# 2022-LPC2148_Piggyback_V1.net
KiCad netlist of a schematic drawn in EAGLE
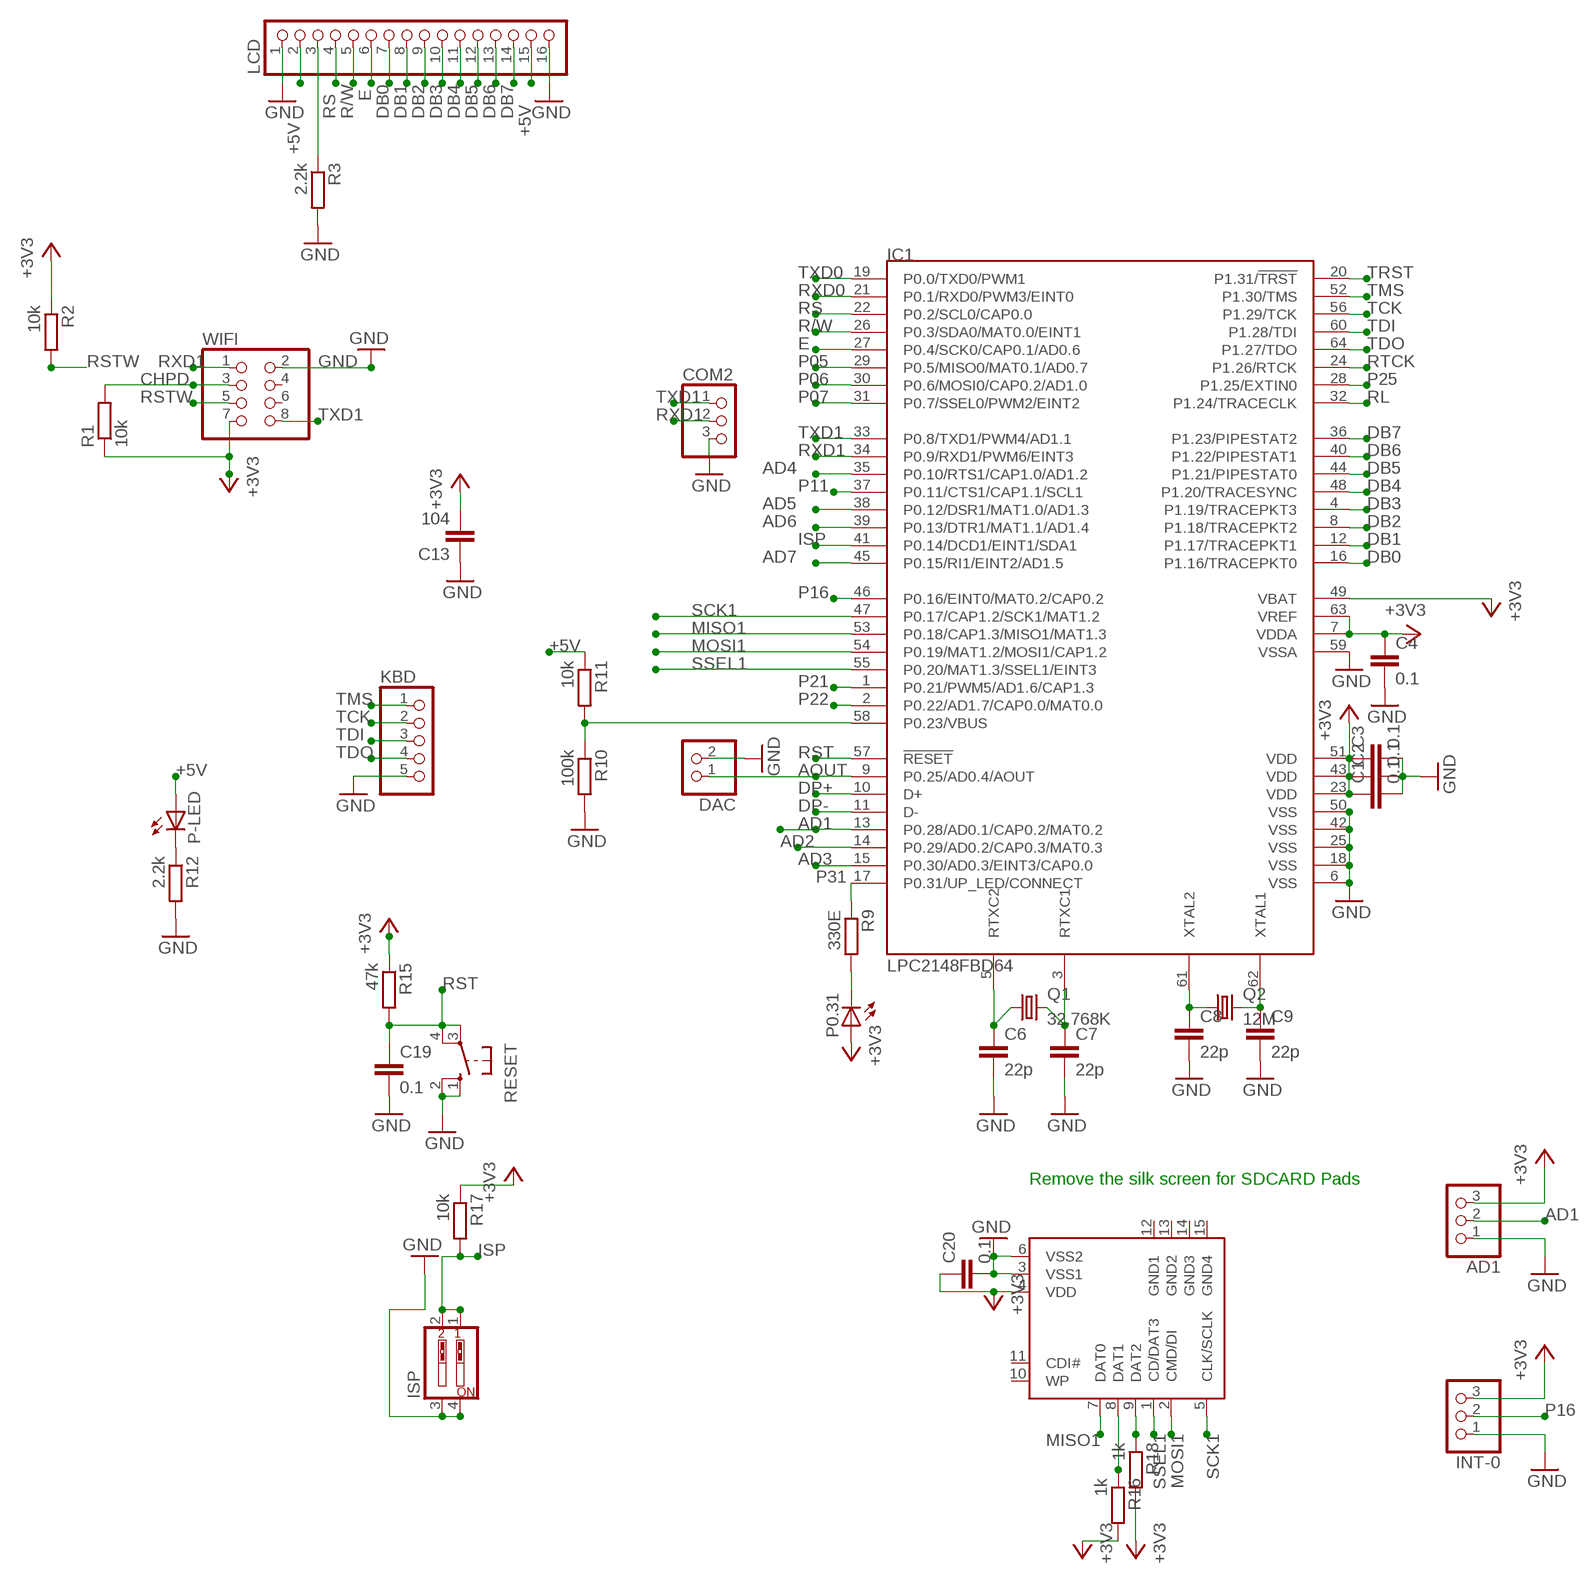
[diagram p0: schematic, sheet 1]
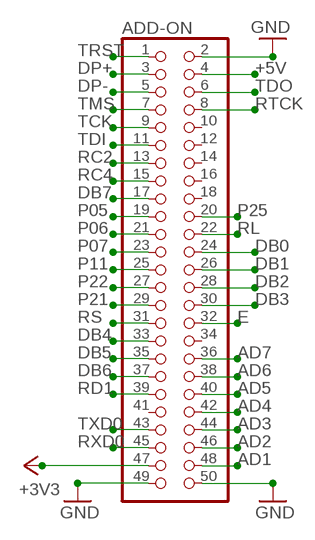
[diagram p1: schematic, sheet 2]
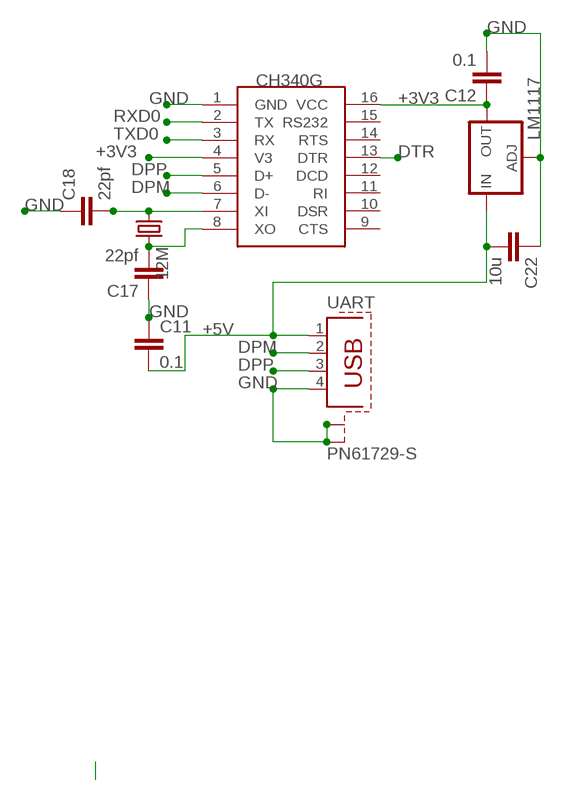
[diagram p2: schematic, sheet 3]

(export (version "E")
  (design (tool "Eeschema 10.0.6"))
  (components
    (comp (ref "AD1")
      (value "PINHD-1X3")
      (footprint "eagle-import:1X03")
      (libsource (lib "eagle-import") (part "PINHD-1X3"))
    )
    (comp (ref "C1")
      (value "0.1")
      (footprint "eagle-import:C1206")
      (libsource (lib "eagle-import") (part "C-EUC1206"))
    )
    (comp (ref "C2")
      (value "0.1")
      (footprint "eagle-import:C1206")
      (libsource (lib "eagle-import") (part "C-EUC1206"))
    )
    (comp (ref "C3")
      (value "0.1")
      (footprint "eagle-import:C1206")
      (libsource (lib "eagle-import") (part "C-EUC1206"))
    )
    (comp (ref "C4")
      (value "0.1")
      (footprint "eagle-import:C1206")
      (libsource (lib "eagle-import") (part "C-EUC1206"))
    )
    (comp (ref "C6")
      (value "22p")
      (footprint "eagle-import:C1206")
      (libsource (lib "eagle-import") (part "C-EUC1206"))
    )
    (comp (ref "C7")
      (value "22p")
      (footprint "eagle-import:C1206")
      (libsource (lib "eagle-import") (part "C-EUC1206"))
    )
    (comp (ref "C8")
      (value "22p")
      (footprint "eagle-import:C1206")
      (libsource (lib "eagle-import") (part "C-EUC1206"))
    )
    (comp (ref "C9")
      (value "22p")
      (footprint "eagle-import:C1206")
      (libsource (lib "eagle-import") (part "C-EUC1206"))
    )
    (comp (ref "C13")
      (value "104")
      (footprint "eagle-import:C1206")
      (libsource (lib "eagle-import") (part "C-EUC1206"))
    )
    (comp (ref "C19")
      (value "0.1")
      (footprint "eagle-import:C1206")
      (libsource (lib "eagle-import") (part "C-EUC1206"))
    )
    (comp (ref "C20")
      (value "0.1")
      (footprint "eagle-import:C1206")
      (libsource (lib "eagle-import") (part "C-EUC1206"))
    )
    (comp (ref "COM2")
      (value "PINHD-1X3")
      (footprint "eagle-import:1X03")
      (libsource (lib "eagle-import") (part "PINHD-1X3"))
    )
    (comp (ref "DAC")
      (value "PINHD-1X2")
      (footprint "eagle-import:1X02")
      (libsource (lib "eagle-import") (part "PINHD-1X2"))
    )
    (comp (ref "IC1")
      (value "LPC2148FBD64")
      (footprint "eagle-import:TSQFP50P1200X1200X160-64N")
      (libsource (lib "eagle-import") (part "LPC2148FBD64"))
    )
    (comp (ref "INT-0")
      (value "PINHD-1X3")
      (footprint "eagle-import:1X03")
      (libsource (lib "eagle-import") (part "PINHD-1X3"))
    )
    (comp (ref "ISP")
      (value "SW_DIP-2")
      (footprint "eagle-import:EDG-02")
      (libsource (lib "eagle-import") (part "SW_DIP-2"))
    )
    (comp (ref "KBD")
      (value "PINHD-1X5")
      (footprint "eagle-import:1X05")
      (libsource (lib "eagle-import") (part "PINHD-1X5"))
    )
    (comp (ref "LCD")
      (value "PINHD-1X16")
      (footprint "eagle-import:1X16")
      (libsource (lib "eagle-import") (part "PINHD-1X16"))
    )
    (comp (ref "P-LED")
      (value "LEDCHIPLED_1206")
      (footprint "eagle-import:CHIPLED_1206")
      (libsource (lib "eagle-import") (part "LEDCHIPLED_1206"))
    )
    (comp (ref "P0.31")
      (value "LEDCHIPLED_1206")
      (footprint "eagle-import:CHIPLED_1206")
      (libsource (lib "eagle-import") (part "LEDCHIPLED_1206"))
    )
    (comp (ref "Q1")
      (value "32.768K")
      (footprint "eagle-import:TC26H")
      (libsource (lib "eagle-import") (part "CRYSTALTC26H"))
    )
    (comp (ref "Q2")
      (value "12M")
      (footprint "eagle-import:HC49U70")
      (libsource (lib "eagle-import") (part "CRYSTALHC49U70"))
    )
    (comp (ref "R1")
      (value "10k")
      (footprint "eagle-import:R1206")
      (libsource (lib "eagle-import") (part "R-EU_R1206"))
    )
    (comp (ref "R2")
      (value "10k")
      (footprint "eagle-import:R1206")
      (libsource (lib "eagle-import") (part "R-EU_R1206"))
    )
    (comp (ref "R3")
      (value "2.2k")
      (footprint "eagle-import:R1206")
      (libsource (lib "eagle-import") (part "R-EU_R1206"))
    )
    (comp (ref "R9")
      (value "330E")
      (footprint "eagle-import:R1206")
      (libsource (lib "eagle-import") (part "R-EU_R1206"))
    )
    (comp (ref "R10")
      (value "100k")
      (footprint "eagle-import:R1206")
      (libsource (lib "eagle-import") (part "R-EU_R1206"))
    )
    (comp (ref "R11")
      (value "10k")
      (footprint "eagle-import:R1206")
      (libsource (lib "eagle-import") (part "R-EU_R1206"))
    )
    (comp (ref "R12")
      (value "2.2k")
      (footprint "eagle-import:R1206")
      (libsource (lib "eagle-import") (part "R-EU_R1206"))
    )
    (comp (ref "R15")
      (value "47k")
      (footprint "eagle-import:R1206")
      (libsource (lib "eagle-import") (part "R-EU_R1206"))
    )
    (comp (ref "R16")
      (value "1k")
      (footprint "eagle-import:R1206")
      (libsource (lib "eagle-import") (part "R-EU_R1206"))
    )
    (comp (ref "R17")
      (value "10k")
      (footprint "eagle-import:R1206")
      (libsource (lib "eagle-import") (part "R-EU_R1206"))
    )
    (comp (ref "R18")
      (value "1k")
      (footprint "eagle-import:R1206")
      (libsource (lib "eagle-import") (part "R-EU_R1206"))
    )
    (comp (ref "RESET")
      (value "10-XX")
      (footprint "eagle-import:B3F-10XX")
      (fields (field (name "MPN") "B3F-1000"))
      (libsource (lib "eagle-import") (part "10-XX"))
    )
    (comp (ref "SD")
      (value "SDCARDVAR2")
      (footprint "eagle-import:SDCMF-10915W010")
      (libsource (lib "eagle-import") (part "SDCARDVAR2"))
    )
    (comp (ref "WIFI")
      (value "PINHD-2X4")
      (footprint "eagle-import:2X04")
      (libsource (lib "eagle-import") (part "PINHD-2X4"))
    )
    (comp (ref "ADD-ON")
      (value "PINHD-2X25")
      (footprint "eagle-import:2X25")
      (libsource (lib "eagle-import") (part "PINHD-2X25"))
    )
    (comp (ref "12M")
      (value "CRYSTALHC18U-V")
      (footprint "eagle-import:HC18U-V")
      (libsource (lib "eagle-import") (part "CRYSTALHC18U-V"))
    )
    (comp (ref "C11")
      (value "0.1")
      (footprint "eagle-import:C1206")
      (libsource (lib "eagle-import") (part "C-EUC1206"))
    )
    (comp (ref "C12")
      (value "0.1")
      (footprint "eagle-import:C1206")
      (libsource (lib "eagle-import") (part "C-EUC1206"))
    )
    (comp (ref "C17")
      (value "22pf")
      (footprint "eagle-import:C1206")
      (libsource (lib "eagle-import") (part "C-EUC1206"))
    )
    (comp (ref "C18")
      (value "22pf")
      (footprint "eagle-import:C1206")
      (libsource (lib "eagle-import") (part "C-EUC1206"))
    )
    (comp (ref "C22")
      (value "10u")
      (footprint "eagle-import:C1206")
      (libsource (lib "eagle-import") (part "C-EUC1206"))
    )
    (comp (ref "LM1117")
      (value "LD117AS18TR")
      (footprint "eagle-import:SOT223")
      (libsource (lib "eagle-import") (part "LD117A?S18TR"))
    )
    (comp (ref "U$1")
      (value "CH340G")
      (footprint "eagle-import:SOIC16")
      (libsource (lib "eagle-import") (part "CH340G"))
    )
    (comp (ref "UART")
      (value "PN61729-S")
      (footprint "eagle-import:PN61729-S")
      (libsource (lib "eagle-import") (part "PN61729-S"))
    )
  )
  (nets
    (net (code "1") (name "+3V3") (class "Default")
      (node (ref "AD1") (pin "3") (pinfunction "3_3") (pintype "passive"))
      (node (ref "ADD-ON") (pin "47") (pinfunction "47_47") (pintype "passive"))
      (node (ref "C1") (pin "1") (pinfunction "1_1") (pintype "passive"))
      (node (ref "C12") (pin "1") (pinfunction "1_1") (pintype "passive"))
      (node (ref "C13") (pin "2") (pinfunction "2_2") (pintype "passive"))
      (node (ref "C2") (pin "1") (pinfunction "1_1") (pintype "passive"))
      (node (ref "C20") (pin "1") (pinfunction "1_1") (pintype "passive"))
      (node (ref "C3") (pin "1") (pinfunction "1_1") (pintype "passive"))
      (node (ref "C4") (pin "1") (pinfunction "1_1") (pintype "passive"))
      (node (ref "IC1") (pin "23") (pinfunction "VDD_23") (pintype "power_in"))
      (node (ref "IC1") (pin "43") (pinfunction "VDD_43") (pintype "power_in"))
      (node (ref "IC1") (pin "49") (pinfunction "VBAT_49") (pintype "power_in"))
      (node (ref "IC1") (pin "51") (pinfunction "VDD_51") (pintype "power_in"))
      (node (ref "IC1") (pin "63") (pinfunction "VREF_63") (pintype "input"))
      (node (ref "IC1") (pin "7") (pinfunction "VDDA_7") (pintype "power_in"))
      (node (ref "INT-0") (pin "3") (pinfunction "3_3") (pintype "passive"))
      (node (ref "LM1117") (pin "4") (pinfunction "OUT_4") (pintype "passive"))
      (node (ref "P0.31") (pin "A") (pinfunction "A_A") (pintype "passive"))
      (node (ref "R1") (pin "1") (pinfunction "1_1") (pintype "passive"))
      (node (ref "R15") (pin "1") (pinfunction "1_1") (pintype "passive"))
      (node (ref "R16") (pin "2") (pinfunction "2_2") (pintype "passive"))
      (node (ref "R17") (pin "1") (pinfunction "1_1") (pintype "passive"))
      (node (ref "R18") (pin "2") (pinfunction "2_2") (pintype "passive"))
      (node (ref "R2") (pin "1") (pinfunction "1_1") (pintype "passive"))
      (node (ref "SD") (pin "4") (pinfunction "VDD_4") (pintype "power_in"))
      (node (ref "U$1") (pin "16") (pinfunction "VCC_16") (pintype "bidirectional"))
      (node (ref "U$1") (pin "4") (pinfunction "V3_4") (pintype "bidirectional"))
      (node (ref "WIFI") (pin "7") (pinfunction "7_7") (pintype "passive"))
    )
    (net (code "2") (name "+5V") (class "Default")
      (node (ref "ADD-ON") (pin "4") (pinfunction "4_4") (pintype "passive"))
      (node (ref "C11") (pin "2") (pinfunction "2_2") (pintype "passive"))
      (node (ref "C22") (pin "2") (pinfunction "2_2") (pintype "passive"))
      (node (ref "LCD") (pin "15") (pinfunction "15_15") (pintype "passive"))
      (node (ref "LCD") (pin "2") (pinfunction "2_2") (pintype "passive"))
      (node (ref "LM1117") (pin "3") (pinfunction "IN_3") (pintype "input"))
      (node (ref "P-LED") (pin "A") (pinfunction "A_A") (pintype "passive"))
      (node (ref "R11") (pin "1") (pinfunction "1_1") (pintype "passive"))
      (node (ref "UART") (pin "1") (pinfunction "1_1") (pintype "passive"))
    )
    (net (code "3") (name "AD1") (class "Default")
      (node (ref "AD1") (pin "2") (pinfunction "2_2") (pintype "passive"))
      (node (ref "ADD-ON") (pin "48") (pinfunction "48_48") (pintype "passive"))
      (node (ref "IC1") (pin "13") (pinfunction "P0.28/AD0.1/CAP0.2/MAT0.2_13") (pintype "bidirectional"))
    )
    (net (code "4") (name "AD2") (class "Default")
      (node (ref "ADD-ON") (pin "46") (pinfunction "46_46") (pintype "passive"))
      (node (ref "IC1") (pin "14") (pinfunction "P0.29/AD0.2/CAP0.3/MAT0.3_14") (pintype "bidirectional"))
    )
    (net (code "5") (name "AD3") (class "Default")
      (node (ref "ADD-ON") (pin "44") (pinfunction "44_44") (pintype "passive"))
      (node (ref "IC1") (pin "15") (pinfunction "P0.30/AD0.3/EINT3/CAP0.0_15") (pintype "bidirectional"))
    )
    (net (code "6") (name "AD4") (class "Default")
      (node (ref "ADD-ON") (pin "42") (pinfunction "42_42") (pintype "passive"))
      (node (ref "IC1") (pin "35") (pinfunction "P0.10/RTS1/CAP1.0/AD1.2_35") (pintype "bidirectional"))
    )
    (net (code "7") (name "AD5") (class "Default")
      (node (ref "ADD-ON") (pin "40") (pinfunction "40_40") (pintype "passive"))
      (node (ref "IC1") (pin "38") (pinfunction "P0.12/DSR1/MAT1.0/AD1.3_38") (pintype "bidirectional"))
    )
    (net (code "8") (name "AD6") (class "Default")
      (node (ref "ADD-ON") (pin "38") (pinfunction "38_38") (pintype "passive"))
      (node (ref "IC1") (pin "39") (pinfunction "P0.13/DTR1/MAT1.1/AD1.4_39") (pintype "bidirectional"))
    )
    (net (code "9") (name "AD7") (class "Default")
      (node (ref "ADD-ON") (pin "36") (pinfunction "36_36") (pintype "passive"))
      (node (ref "IC1") (pin "45") (pinfunction "P0.15/RI1/EINT2/AD1.5_45") (pintype "bidirectional"))
    )
    (net (code "10") (name "AOUT") (class "Default")
      (node (ref "DAC") (pin "1") (pinfunction "1_1") (pintype "passive"))
      (node (ref "IC1") (pin "9") (pinfunction "P0.25/AD0.4/AOUT_9") (pintype "bidirectional"))
    )
    (net (code "11") (name "CHPD") (class "Default")
      (node (ref "R1") (pin "2") (pinfunction "2_2") (pintype "passive"))
      (node (ref "WIFI") (pin "3") (pinfunction "3_3") (pintype "passive"))
    )
    (net (code "12") (name "DB0") (class "Default")
      (node (ref "ADD-ON") (pin "24") (pinfunction "24_24") (pintype "passive"))
      (node (ref "IC1") (pin "16") (pinfunction "P1.16/TRACEPKT0_16") (pintype "bidirectional"))
      (node (ref "LCD") (pin "7") (pinfunction "7_7") (pintype "passive"))
    )
    (net (code "13") (name "DB1") (class "Default")
      (node (ref "ADD-ON") (pin "26") (pinfunction "26_26") (pintype "passive"))
      (node (ref "IC1") (pin "12") (pinfunction "P1.17/TRACEPKT1_12") (pintype "bidirectional"))
      (node (ref "LCD") (pin "8") (pinfunction "8_8") (pintype "passive"))
    )
    (net (code "14") (name "DB2") (class "Default")
      (node (ref "ADD-ON") (pin "28") (pinfunction "28_28") (pintype "passive"))
      (node (ref "IC1") (pin "8") (pinfunction "P1.18/TRACEPKT2_8") (pintype "bidirectional"))
      (node (ref "LCD") (pin "9") (pinfunction "9_9") (pintype "passive"))
    )
    (net (code "15") (name "DB3") (class "Default")
      (node (ref "ADD-ON") (pin "30") (pinfunction "30_30") (pintype "passive"))
      (node (ref "IC1") (pin "4") (pinfunction "P1.19/TRACEPKT3_4") (pintype "bidirectional"))
      (node (ref "LCD") (pin "10") (pinfunction "10_10") (pintype "passive"))
    )
    (net (code "16") (name "DB4") (class "Default")
      (node (ref "ADD-ON") (pin "33") (pinfunction "33_33") (pintype "passive"))
      (node (ref "IC1") (pin "48") (pinfunction "P1.20/TRACESYNC_48") (pintype "bidirectional"))
      (node (ref "LCD") (pin "11") (pinfunction "11_11") (pintype "passive"))
    )
    (net (code "17") (name "DB5") (class "Default")
      (node (ref "ADD-ON") (pin "35") (pinfunction "35_35") (pintype "passive"))
      (node (ref "IC1") (pin "44") (pinfunction "P1.21/PIPESTAT0_44") (pintype "bidirectional"))
      (node (ref "LCD") (pin "12") (pinfunction "12_12") (pintype "passive"))
    )
    (net (code "18") (name "DB6") (class "Default")
      (node (ref "ADD-ON") (pin "37") (pinfunction "37_37") (pintype "passive"))
      (node (ref "IC1") (pin "40") (pinfunction "P1.22/PIPESTAT1_40") (pintype "bidirectional"))
      (node (ref "LCD") (pin "13") (pinfunction "13_13") (pintype "passive"))
    )
    (net (code "19") (name "DB7") (class "Default")
      (node (ref "ADD-ON") (pin "17") (pinfunction "17_17") (pintype "passive"))
      (node (ref "IC1") (pin "36") (pinfunction "P1.23/PIPESTAT2_36") (pintype "bidirectional"))
      (node (ref "LCD") (pin "14") (pinfunction "14_14") (pintype "passive"))
    )
    (net (code "20") (name "DP+") (class "Default")
      (node (ref "ADD-ON") (pin "3") (pinfunction "3_3") (pintype "passive"))
      (node (ref "IC1") (pin "10") (pinfunction "D+_10") (pintype "bidirectional"))
    )
    (net (code "21") (name "DP-") (class "Default")
      (node (ref "ADD-ON") (pin "5") (pinfunction "5_5") (pintype "passive"))
      (node (ref "IC1") (pin "11") (pinfunction "D-_11") (pintype "bidirectional"))
    )
    (net (code "22") (name "DPM") (class "Default")
      (node (ref "U$1") (pin "6") (pinfunction "D-_6") (pintype "bidirectional"))
      (node (ref "UART") (pin "2") (pinfunction "2_2") (pintype "passive"))
    )
    (net (code "23") (name "DPP") (class "Default")
      (node (ref "U$1") (pin "5") (pinfunction "D+_5") (pintype "bidirectional"))
      (node (ref "UART") (pin "3") (pinfunction "3_3") (pintype "passive"))
    )
    (net (code "24") (name "DTR") (class "Default")
      (node (ref "U$1") (pin "13") (pinfunction "DTR_13") (pintype "bidirectional"))
    )
    (net (code "25") (name "E") (class "Default")
      (node (ref "ADD-ON") (pin "32") (pinfunction "32_32") (pintype "passive"))
      (node (ref "IC1") (pin "27") (pinfunction "P0.4/SCK0/CAP0.1/AD0.6_27") (pintype "bidirectional"))
      (node (ref "LCD") (pin "6") (pinfunction "6_6") (pintype "passive"))
    )
    (net (code "26") (name "GND") (class "Default")
      (node (ref "AD1") (pin "1") (pinfunction "1_1") (pintype "passive"))
      (node (ref "ADD-ON") (pin "2") (pinfunction "2_2") (pintype "passive"))
      (node (ref "ADD-ON") (pin "49") (pinfunction "49_49") (pintype "passive"))
      (node (ref "ADD-ON") (pin "50") (pinfunction "50_50") (pintype "passive"))
      (node (ref "C1") (pin "2") (pinfunction "2_2") (pintype "passive"))
      (node (ref "C11") (pin "1") (pinfunction "1_1") (pintype "passive"))
      (node (ref "C12") (pin "2") (pinfunction "2_2") (pintype "passive"))
      (node (ref "C13") (pin "1") (pinfunction "1_1") (pintype "passive"))
      (node (ref "C17") (pin "1") (pinfunction "1_1") (pintype "passive"))
      (node (ref "C18") (pin "1") (pinfunction "1_1") (pintype "passive"))
      (node (ref "C19") (pin "2") (pinfunction "2_2") (pintype "passive"))
      (node (ref "C2") (pin "2") (pinfunction "2_2") (pintype "passive"))
      (node (ref "C20") (pin "2") (pinfunction "2_2") (pintype "passive"))
      (node (ref "C22") (pin "1") (pinfunction "1_1") (pintype "passive"))
      (node (ref "C3") (pin "2") (pinfunction "2_2") (pintype "passive"))
      (node (ref "C4") (pin "2") (pinfunction "2_2") (pintype "passive"))
      (node (ref "C6") (pin "2") (pinfunction "2_2") (pintype "passive"))
      (node (ref "C7") (pin "2") (pinfunction "2_2") (pintype "passive"))
      (node (ref "C8") (pin "2") (pinfunction "2_2") (pintype "passive"))
      (node (ref "C9") (pin "2") (pinfunction "2_2") (pintype "passive"))
      (node (ref "COM2") (pin "3") (pinfunction "3_3") (pintype "passive"))
      (node (ref "DAC") (pin "2") (pinfunction "2_2") (pintype "passive"))
      (node (ref "IC1") (pin "18") (pinfunction "VSS_18") (pintype "power_in"))
      (node (ref "IC1") (pin "25") (pinfunction "VSS_25") (pintype "power_in"))
      (node (ref "IC1") (pin "42") (pinfunction "VSS_42") (pintype "power_in"))
      (node (ref "IC1") (pin "50") (pinfunction "VSS_50") (pintype "power_in"))
      (node (ref "IC1") (pin "59") (pinfunction "VSSA_59") (pintype "power_in"))
      (node (ref "IC1") (pin "6") (pinfunction "VSS_6") (pintype "power_in"))
      (node (ref "INT-0") (pin "1") (pinfunction "1_1") (pintype "passive"))
      (node (ref "ISP") (pin "3") (pinfunction "3_3") (pintype "passive"))
      (node (ref "ISP") (pin "4") (pinfunction "4_4") (pintype "passive"))
      (node (ref "KBD") (pin "5") (pinfunction "5_5") (pintype "passive"))
      (node (ref "LCD") (pin "1") (pinfunction "1_1") (pintype "passive"))
      (node (ref "LCD") (pin "16") (pinfunction "16_16") (pintype "passive"))
      (node (ref "LM1117") (pin "1") (pinfunction "ADJ_1") (pintype "input"))
      (node (ref "R10") (pin "2") (pinfunction "2_2") (pintype "passive"))
      (node (ref "R12") (pin "2") (pinfunction "2_2") (pintype "passive"))
      (node (ref "R3") (pin "2") (pinfunction "2_2") (pintype "passive"))
      (node (ref "RESET") (pin "1") (pinfunction "S_1") (pintype "passive"))
      (node (ref "RESET") (pin "2") (pinfunction "S1_2") (pintype "passive"))
      (node (ref "SD") (pin "3") (pinfunction "VSS1_3") (pintype "power_in"))
      (node (ref "SD") (pin "6") (pinfunction "VSS2_6") (pintype "power_in"))
      (node (ref "U$1") (pin "1") (pinfunction "GND_1") (pintype "bidirectional"))
      (node (ref "UART") (pin "4") (pinfunction "4_4") (pintype "passive"))
      (node (ref "UART") (pin "S1") (pinfunction "S1_S1") (pintype "passive"))
      (node (ref "UART") (pin "S2") (pinfunction "S2_S2") (pintype "passive"))
      (node (ref "WIFI") (pin "2") (pinfunction "2_2") (pintype "passive"))
    )
    (net (code "27") (name "GND1") (class "Default")
      (node (ref "SD") (pin "12") (pinfunction "GND1_12") (pintype "power_in"))
    )
    (net (code "28") (name "GND2") (class "Default")
      (node (ref "SD") (pin "13") (pinfunction "GND2_13") (pintype "power_in"))
    )
    (net (code "29") (name "GND3") (class "Default")
      (node (ref "SD") (pin "14") (pinfunction "GND3_14") (pintype "power_in"))
    )
    (net (code "30") (name "GND4") (class "Default")
      (node (ref "SD") (pin "15") (pinfunction "GND4_15") (pintype "power_in"))
    )
    (net (code "31") (name "ISP") (class "Default")
      (node (ref "IC1") (pin "41") (pinfunction "P0.14/DCD1/EINT1/SDA1_41") (pintype "bidirectional"))
      (node (ref "ISP") (pin "1") (pinfunction "1_1") (pintype "passive"))
      (node (ref "ISP") (pin "2") (pinfunction "2_2") (pintype "passive"))
      (node (ref "R17") (pin "2") (pinfunction "2_2") (pintype "passive"))
    )
    (net (code "32") (name "MISO1") (class "Default")
      (node (ref "IC1") (pin "53") (pinfunction "P0.18/CAP1.3/MISO1/MAT1.3_53") (pintype "bidirectional"))
      (node (ref "SD") (pin "7") (pinfunction "DAT0_7") (pintype "bidirectional"))
    )
    (net (code "33") (name "MOSI1") (class "Default")
      (node (ref "IC1") (pin "54") (pinfunction "P0.19/MAT1.2/MOSI1/CAP1.2_54") (pintype "bidirectional"))
      (node (ref "SD") (pin "2") (pinfunction "CMD/DI_2") (pintype "bidirectional"))
    )
    (net (code "34") (name "Net-(IC1-P0.23{slash}VBUS)") (class "Default")
      (node (ref "IC1") (pin "58") (pinfunction "P0.23/VBUS_58") (pintype "bidirectional"))
      (node (ref "R10") (pin "1") (pinfunction "1_1") (pintype "passive"))
      (node (ref "R11") (pin "2") (pinfunction "2_2") (pintype "passive"))
    )
    (net (code "35") (name "Net-(IC1-RTXC1)") (class "Default")
      (node (ref "C7") (pin "1") (pinfunction "1_1") (pintype "passive"))
      (node (ref "IC1") (pin "3") (pinfunction "RTXC1_3") (pintype "input"))
      (node (ref "Q1") (pin "2") (pinfunction "2_2") (pintype "passive"))
    )
    (net (code "36") (name "Net-(IC1-RTXC2)") (class "Default")
      (node (ref "C6") (pin "1") (pinfunction "1_1") (pintype "passive"))
      (node (ref "IC1") (pin "5") (pinfunction "RTXC2_5") (pintype "output"))
      (node (ref "Q1") (pin "1") (pinfunction "1_1") (pintype "passive"))
    )
    (net (code "37") (name "Net-(IC1-XTAL1)") (class "Default")
      (node (ref "C9") (pin "1") (pinfunction "1_1") (pintype "passive"))
      (node (ref "IC1") (pin "62") (pinfunction "XTAL1_62") (pintype "input"))
      (node (ref "Q2") (pin "2") (pinfunction "2_2") (pintype "passive"))
    )
    (net (code "38") (name "Net-(IC1-XTAL2)") (class "Default")
      (node (ref "C8") (pin "1") (pinfunction "1_1") (pintype "passive"))
      (node (ref "IC1") (pin "61") (pinfunction "XTAL2_61") (pintype "output"))
      (node (ref "Q2") (pin "1") (pinfunction "1_1") (pintype "passive"))
    )
    (net (code "39") (name "Net-(LCD-Pad3)") (class "Default")
      (node (ref "LCD") (pin "3") (pinfunction "3_3") (pintype "passive"))
      (node (ref "R3") (pin "1") (pinfunction "1_1") (pintype "passive"))
    )
    (net (code "40") (name "Net-(P-LED-PadC)") (class "Default")
      (node (ref "P-LED") (pin "C") (pinfunction "C_C") (pintype "passive"))
      (node (ref "R12") (pin "1") (pinfunction "1_1") (pintype "passive"))
    )
    (net (code "41") (name "Net-(P0.31-PadC)") (class "Default")
      (node (ref "P0.31") (pin "C") (pinfunction "C_C") (pintype "passive"))
      (node (ref "R9") (pin "2") (pinfunction "2_2") (pintype "passive"))
    )
    (net (code "42") (name "Net-(SD-DAT1)") (class "Default")
      (node (ref "R16") (pin "1") (pinfunction "1_1") (pintype "passive"))
      (node (ref "SD") (pin "8") (pinfunction "DAT1_8") (pintype "bidirectional"))
    )
    (net (code "43") (name "Net-(SD-DAT2)") (class "Default")
      (node (ref "R18") (pin "1") (pinfunction "1_1") (pintype "passive"))
      (node (ref "SD") (pin "9") (pinfunction "DAT2_9") (pintype "bidirectional"))
    )
    (net (code "44") (name "Net-(U$1-XI)") (class "Default")
      (node (ref "12M") (pin "1") (pinfunction "1_1") (pintype "passive"))
      (node (ref "C18") (pin "2") (pinfunction "2_2") (pintype "passive"))
      (node (ref "U$1") (pin "7") (pinfunction "XI_7") (pintype "bidirectional"))
    )
    (net (code "45") (name "Net-(U$1-XO)") (class "Default")
      (node (ref "12M") (pin "2") (pinfunction "2_2") (pintype "passive"))
      (node (ref "C17") (pin "2") (pinfunction "2_2") (pintype "passive"))
      (node (ref "U$1") (pin "8") (pinfunction "XO_8") (pintype "bidirectional"))
    )
    (net (code "46") (name "P05") (class "Default")
      (node (ref "ADD-ON") (pin "19") (pinfunction "19_19") (pintype "passive"))
      (node (ref "IC1") (pin "29") (pinfunction "P0.5/MISO0/MAT0.1/AD0.7_29") (pintype "bidirectional"))
    )
    (net (code "47") (name "P06") (class "Default")
      (node (ref "ADD-ON") (pin "21") (pinfunction "21_21") (pintype "passive"))
      (node (ref "IC1") (pin "30") (pinfunction "P0.6/MOSI0/CAP0.2/AD1.0_30") (pintype "bidirectional"))
    )
    (net (code "48") (name "P07") (class "Default")
      (node (ref "ADD-ON") (pin "23") (pinfunction "23_23") (pintype "passive"))
      (node (ref "IC1") (pin "31") (pinfunction "P0.7/SSEL0/PWM2/EINT2_31") (pintype "bidirectional"))
    )
    (net (code "49") (name "P11") (class "Default")
      (node (ref "ADD-ON") (pin "25") (pinfunction "25_25") (pintype "passive"))
      (node (ref "IC1") (pin "37") (pinfunction "P0.11/CTS1/CAP1.1/SCL1_37") (pintype "bidirectional"))
    )
    (net (code "50") (name "P16") (class "Default")
      (node (ref "IC1") (pin "46") (pinfunction "P0.16/EINT0/MAT0.2/CAP0.2_46") (pintype "bidirectional"))
      (node (ref "INT-0") (pin "2") (pinfunction "2_2") (pintype "passive"))
    )
    (net (code "51") (name "P21") (class "Default")
      (node (ref "ADD-ON") (pin "29") (pinfunction "29_29") (pintype "passive"))
      (node (ref "IC1") (pin "1") (pinfunction "P0.21/PWM5/AD1.6/CAP1.3_1") (pintype "bidirectional"))
    )
    (net (code "52") (name "P22") (class "Default")
      (node (ref "ADD-ON") (pin "27") (pinfunction "27_27") (pintype "passive"))
      (node (ref "IC1") (pin "2") (pinfunction "P0.22/AD1.7/CAP0.0/MAT0.0_2") (pintype "bidirectional"))
    )
    (net (code "53") (name "P25") (class "Default")
      (node (ref "ADD-ON") (pin "20") (pinfunction "20_20") (pintype "passive"))
      (node (ref "IC1") (pin "28") (pinfunction "P1.25/EXTIN0_28") (pintype "bidirectional"))
    )
    (net (code "54") (name "P31") (class "Default")
      (node (ref "IC1") (pin "17") (pinfunction "P0.31/UP_LED/CONNECT_17") (pintype "bidirectional"))
      (node (ref "R9") (pin "1") (pinfunction "1_1") (pintype "passive"))
    )
    (net (code "55") (name "RC2") (class "Default")
      (node (ref "ADD-ON") (pin "13") (pinfunction "13_13") (pintype "passive"))
    )
    (net (code "56") (name "RC4") (class "Default")
      (node (ref "ADD-ON") (pin "15") (pinfunction "15_15") (pintype "passive"))
    )
    (net (code "57") (name "RD1") (class "Default")
      (node (ref "ADD-ON") (pin "39") (pinfunction "39_39") (pintype "passive"))
    )
    (net (code "58") (name "RL") (class "Default")
      (node (ref "ADD-ON") (pin "22") (pinfunction "22_22") (pintype "passive"))
      (node (ref "IC1") (pin "32") (pinfunction "P1.24/TRACECLK_32") (pintype "bidirectional"))
    )
    (net (code "59") (name "RS") (class "Default")
      (node (ref "ADD-ON") (pin "31") (pinfunction "31_31") (pintype "passive"))
      (node (ref "IC1") (pin "22") (pinfunction "P0.2/SCL0/CAP0.0_22") (pintype "bidirectional"))
      (node (ref "LCD") (pin "4") (pinfunction "4_4") (pintype "passive"))
    )
    (net (code "60") (name "RST") (class "Default")
      (node (ref "C19") (pin "1") (pinfunction "1_1") (pintype "passive"))
      (node (ref "IC1") (pin "57") (pinfunction "~{RESET}_57") (pintype "input"))
      (node (ref "R15") (pin "2") (pinfunction "2_2") (pintype "passive"))
      (node (ref "RESET") (pin "3") (pinfunction "P_3") (pintype "passive"))
      (node (ref "RESET") (pin "4") (pinfunction "P1_4") (pintype "passive"))
    )
    (net (code "61") (name "RSTW") (class "Default")
      (node (ref "R2") (pin "2") (pinfunction "2_2") (pintype "passive"))
      (node (ref "WIFI") (pin "5") (pinfunction "5_5") (pintype "passive"))
    )
    (net (code "62") (name "RTCK") (class "Default")
      (node (ref "ADD-ON") (pin "8") (pinfunction "8_8") (pintype "passive"))
      (node (ref "IC1") (pin "24") (pinfunction "P1.26/RTCK_24") (pintype "bidirectional"))
    )
    (net (code "63") (name "RXD0") (class "Default")
      (node (ref "ADD-ON") (pin "45") (pinfunction "45_45") (pintype "passive"))
      (node (ref "IC1") (pin "21") (pinfunction "P0.1/RXD0/PWM3/EINT0_21") (pintype "bidirectional"))
      (node (ref "U$1") (pin "2") (pinfunction "TX_2") (pintype "bidirectional"))
    )
    (net (code "64") (name "RXD1") (class "Default")
      (node (ref "COM2") (pin "2") (pinfunction "2_2") (pintype "passive"))
      (node (ref "IC1") (pin "34") (pinfunction "P0.9/RXD1/PWM6/EINT3_34") (pintype "bidirectional"))
      (node (ref "WIFI") (pin "1") (pinfunction "1_1") (pintype "passive"))
    )
    (net (code "65") (name "R{slash}W") (class "Default")
      (node (ref "IC1") (pin "26") (pinfunction "P0.3/SDA0/MAT0.0/EINT1_26") (pintype "bidirectional"))
      (node (ref "LCD") (pin "5") (pinfunction "5_5") (pintype "passive"))
    )
    (net (code "66") (name "SCK1") (class "Default")
      (node (ref "IC1") (pin "47") (pinfunction "P0.17/CAP1.2/SCK1/MAT1.2_47") (pintype "bidirectional"))
      (node (ref "SD") (pin "5") (pinfunction "CLK/SCLK_5") (pintype "bidirectional"))
    )
    (net (code "67") (name "SSEL1") (class "Default")
      (node (ref "IC1") (pin "55") (pinfunction "P0.20/MAT1.3/SSEL1/EINT3_55") (pintype "bidirectional"))
      (node (ref "SD") (pin "1") (pinfunction "CD/DAT3_1") (pintype "bidirectional"))
    )
    (net (code "68") (name "TCK") (class "Default")
      (node (ref "ADD-ON") (pin "9") (pinfunction "9_9") (pintype "passive"))
      (node (ref "IC1") (pin "56") (pinfunction "P1.29/TCK_56") (pintype "bidirectional"))
      (node (ref "KBD") (pin "2") (pinfunction "2_2") (pintype "passive"))
    )
    (net (code "69") (name "TDI") (class "Default")
      (node (ref "ADD-ON") (pin "11") (pinfunction "11_11") (pintype "passive"))
      (node (ref "IC1") (pin "60") (pinfunction "P1.28/TDI_60") (pintype "bidirectional"))
      (node (ref "KBD") (pin "3") (pinfunction "3_3") (pintype "passive"))
    )
    (net (code "70") (name "TDO") (class "Default")
      (node (ref "ADD-ON") (pin "6") (pinfunction "6_6") (pintype "passive"))
      (node (ref "IC1") (pin "64") (pinfunction "P1.27/TDO_64") (pintype "bidirectional"))
      (node (ref "KBD") (pin "4") (pinfunction "4_4") (pintype "passive"))
    )
    (net (code "71") (name "TMS") (class "Default")
      (node (ref "ADD-ON") (pin "7") (pinfunction "7_7") (pintype "passive"))
      (node (ref "IC1") (pin "52") (pinfunction "P1.30/TMS_52") (pintype "bidirectional"))
      (node (ref "KBD") (pin "1") (pinfunction "1_1") (pintype "passive"))
    )
    (net (code "72") (name "TRST") (class "Default")
      (node (ref "ADD-ON") (pin "1") (pinfunction "1_1") (pintype "passive"))
      (node (ref "IC1") (pin "20") (pinfunction "P1.31/~{TRST}_20") (pintype "bidirectional"))
    )
    (net (code "73") (name "TXD0") (class "Default")
      (node (ref "ADD-ON") (pin "43") (pinfunction "43_43") (pintype "passive"))
      (node (ref "IC1") (pin "19") (pinfunction "P0.0/TXD0/PWM1_19") (pintype "bidirectional"))
      (node (ref "U$1") (pin "3") (pinfunction "RX_3") (pintype "bidirectional"))
    )
    (net (code "74") (name "TXD1") (class "Default")
      (node (ref "COM2") (pin "1") (pinfunction "1_1") (pintype "passive"))
      (node (ref "IC1") (pin "33") (pinfunction "P0.8/TXD1/PWM4/AD1.1_33") (pintype "bidirectional"))
      (node (ref "WIFI") (pin "8") (pinfunction "8_8") (pintype "passive"))
    )
    (net (code "75") (name "unconnected-(ADD-ON-Pad10)") (class "Default")
      (node (ref "ADD-ON") (pin "10") (pinfunction "10_10") (pintype "passive"))
    )
    (net (code "76") (name "unconnected-(ADD-ON-Pad12)") (class "Default")
      (node (ref "ADD-ON") (pin "12") (pinfunction "12_12") (pintype "passive"))
    )
    (net (code "77") (name "unconnected-(ADD-ON-Pad14)") (class "Default")
      (node (ref "ADD-ON") (pin "14") (pinfunction "14_14") (pintype "passive"))
    )
    (net (code "78") (name "unconnected-(ADD-ON-Pad16)") (class "Default")
      (node (ref "ADD-ON") (pin "16") (pinfunction "16_16") (pintype "passive"))
    )
    (net (code "79") (name "unconnected-(ADD-ON-Pad18)") (class "Default")
      (node (ref "ADD-ON") (pin "18") (pinfunction "18_18") (pintype "passive"))
    )
    (net (code "80") (name "unconnected-(ADD-ON-Pad34)") (class "Default")
      (node (ref "ADD-ON") (pin "34") (pinfunction "34_34") (pintype "passive"))
    )
    (net (code "81") (name "unconnected-(ADD-ON-Pad41)") (class "Default")
      (node (ref "ADD-ON") (pin "41") (pinfunction "41_41") (pintype "passive"))
    )
    (net (code "82") (name "unconnected-(SD-CDI#-Pad11)") (class "Default")
      (node (ref "SD") (pin "11") (pinfunction "CDI#_11") (pintype "output"))
    )
    (net (code "83") (name "unconnected-(SD-WP-Pad10)") (class "Default")
      (node (ref "SD") (pin "10") (pinfunction "WP_10") (pintype "output"))
    )
    (net (code "84") (name "unconnected-(U$1-CTS-Pad9)") (class "Default")
      (node (ref "U$1") (pin "9") (pinfunction "CTS_9") (pintype "bidirectional"))
    )
    (net (code "85") (name "unconnected-(U$1-DCD-Pad12)") (class "Default")
      (node (ref "U$1") (pin "12") (pinfunction "DCD_12") (pintype "bidirectional"))
    )
    (net (code "86") (name "unconnected-(U$1-DSR-Pad10)") (class "Default")
      (node (ref "U$1") (pin "10") (pinfunction "DSR_10") (pintype "bidirectional"))
    )
    (net (code "87") (name "unconnected-(U$1-RI-Pad11)") (class "Default")
      (node (ref "U$1") (pin "11") (pinfunction "RI_11") (pintype "bidirectional"))
    )
    (net (code "88") (name "unconnected-(U$1-RS232-Pad15)") (class "Default")
      (node (ref "U$1") (pin "15") (pinfunction "RS232_15") (pintype "bidirectional"))
    )
    (net (code "89") (name "unconnected-(U$1-RTS-Pad14)") (class "Default")
      (node (ref "U$1") (pin "14") (pinfunction "RTS_14") (pintype "bidirectional"))
    )
    (net (code "90") (name "unconnected-(WIFI-Pad4)") (class "Default")
      (node (ref "WIFI") (pin "4") (pinfunction "4_4") (pintype "passive"))
    )
    (net (code "91") (name "unconnected-(WIFI-Pad6)") (class "Default")
      (node (ref "WIFI") (pin "6") (pinfunction "6_6") (pintype "passive"))
    )
  )
)
